# User_-_Input.net
KiCad netlist of a schematic drawn in Altium Designer
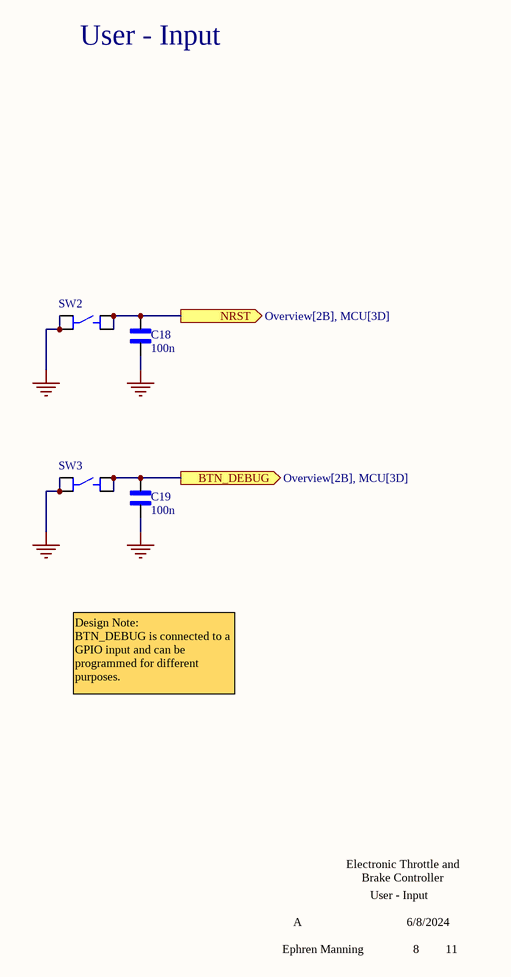
[diagram p0: User - Input.SchDoc]

(export (version "E")
  (design (tool "Eeschema 10.0.6"))
  (components
    (comp (ref "C18")
      (value "100n")
      (footprint "CAP_0402-Footprint-1")
      (description "100nF 10V 10% 0402 CAP")
      (fields (field (name "DIGIKEY PART NUMBER") "1276-1002-1-ND"))
      (libsource (lib "SAE @ UIC Formula Electric") (part "CAP_0402-Symbol-1"))
    )
    (comp (ref "C19")
      (value "100n")
      (footprint "CAP_0402-Footprint-1")
      (description "100nF 10V 10% 0402 CAP")
      (fields (field (name "DIGIKEY PART NUMBER") "1276-1002-1-ND"))
      (libsource (lib "SAE @ UIC Formula Electric") (part "CAP_0402-Symbol-1"))
    )
    (comp (ref "SW2")
      (value "PTS810_SJM_250_SMTR_LFS")
      (footprint "SW_PTS810_SJM_250_SMTR_LFS")
      (description "Tactile Switch SPST-NO Top Actuated Surface Mount")
      (fields (field (name "DIGIKEY PART NUMBER") "CKN10502CT-ND"))
      (libsource (lib "SAE @ UIC Formula Electric") (part "PTS810_SJM_250_SMTR_LFS"))
    )
    (comp (ref "SW3")
      (value "PTS810_SJM_250_SMTR_LFS")
      (footprint "SW_PTS810_SJM_250_SMTR_LFS")
      (description "Tactile Switch SPST-NO Top Actuated Surface Mount")
      (fields (field (name "DIGIKEY PART NUMBER") "CKN10502CT-ND"))
      (libsource (lib "SAE @ UIC Formula Electric") (part "PTS810_SJM_250_SMTR_LFS"))
    )
  )
  (nets
    (net (code "1") (name "/BTN_DEBUG") (class "Default")
      (node (ref "C19") (pin "2") (pinfunction "2_2") (pintype "passive"))
      (node (ref "SW3") (pin "3") (pinfunction "3_3") (pintype "passive"))
      (node (ref "SW3") (pin "4") (pinfunction "4_4") (pintype "passive"))
    )
    (net (code "2") (name "/NRST") (class "Default")
      (node (ref "C18") (pin "2") (pinfunction "2_2") (pintype "passive"))
      (node (ref "SW2") (pin "3") (pinfunction "3_3") (pintype "passive"))
      (node (ref "SW2") (pin "4") (pinfunction "4_4") (pintype "passive"))
    )
    (net (code "3") (name "GND") (class "Default")
      (node (ref "C18") (pin "1") (pinfunction "1_1") (pintype "passive"))
      (node (ref "C19") (pin "1") (pinfunction "1_1") (pintype "passive"))
      (node (ref "SW2") (pin "1") (pinfunction "1_1") (pintype "passive"))
      (node (ref "SW2") (pin "2") (pinfunction "2_2") (pintype "passive"))
      (node (ref "SW3") (pin "1") (pinfunction "1_1") (pintype "passive"))
      (node (ref "SW3") (pin "2") (pinfunction "2_2") (pintype "passive"))
    )
  )
)
